# L9110_v1_1.net
KiCad netlist of a schematic drawn in EAGLE
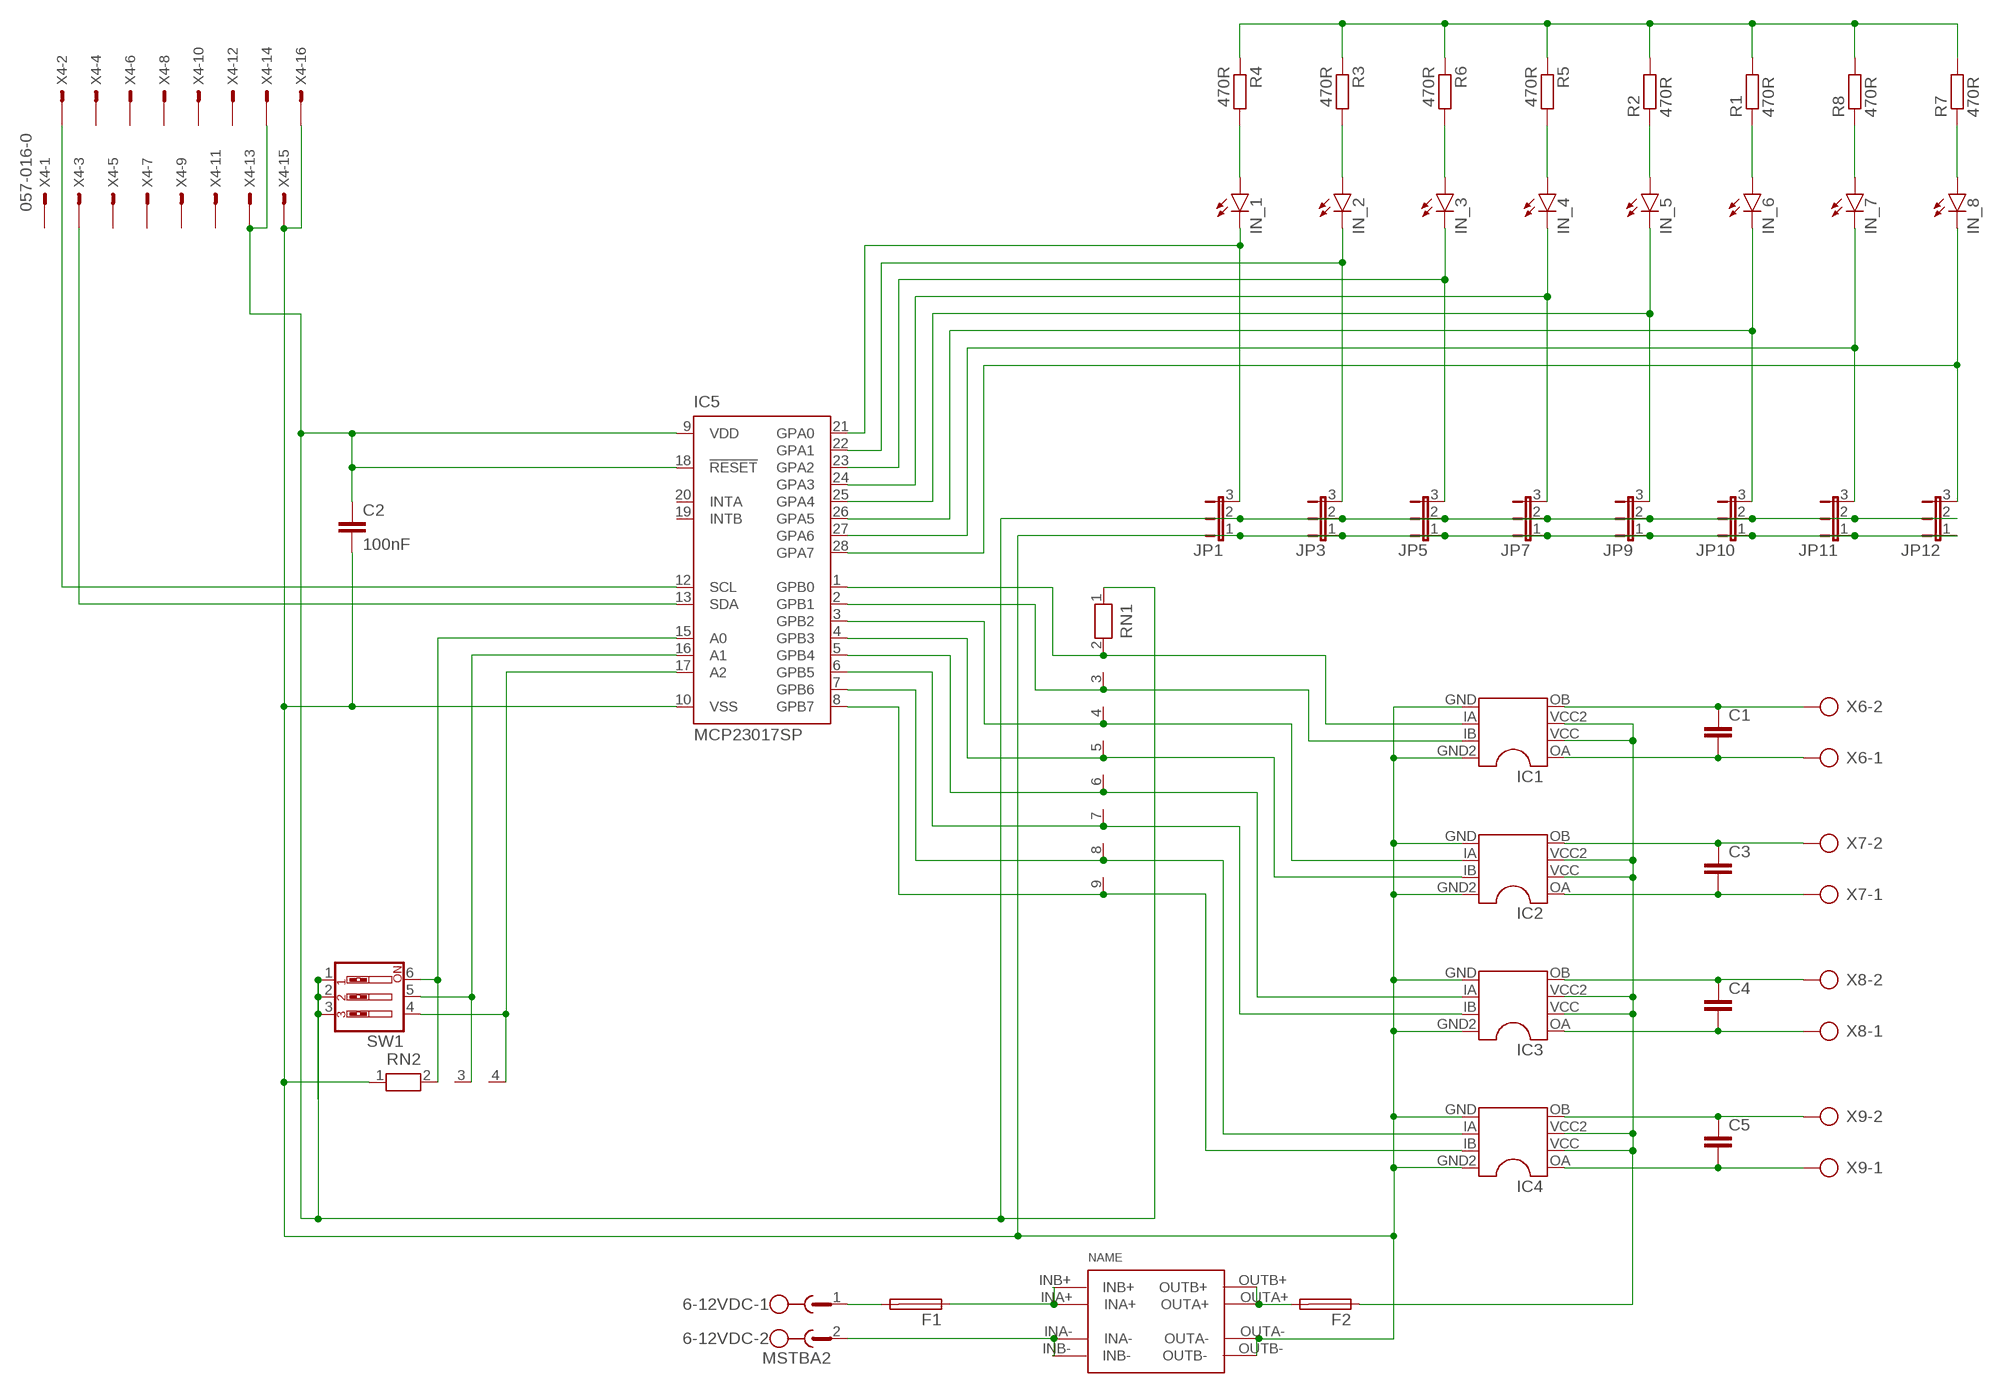
[diagram p0: schematic, sheet 1]

(export (version "E")
  (design (tool "Eeschema 10.0.6"))
  (components
    (comp (ref "6-12VDC")
      (value "MSTBA2")
      (footprint "eagle-import:MSTBA2")
      (fields (field (name "MF") "FARNELL") (field (name "MPN") "1757242"))
      (libsource (lib "eagle-import") (part "MSTBA2"))
    )
    (comp (ref "C1")
      (value "C-EU025-024X044")
      (footprint "eagle-import:C025-024X044")
      (libsource (lib "eagle-import") (part "C-EU025-024X044"))
    )
    (comp (ref "C2")
      (value "100nF")
      (footprint "eagle-import:C025-024X044")
      (libsource (lib "eagle-import") (part "C-EU025-024X044"))
    )
    (comp (ref "C3")
      (value "C-EU025-024X044")
      (footprint "eagle-import:C025-024X044")
      (libsource (lib "eagle-import") (part "C-EU025-024X044"))
    )
    (comp (ref "C4")
      (value "C-EU025-024X044")
      (footprint "eagle-import:C025-024X044")
      (libsource (lib "eagle-import") (part "C-EU025-024X044"))
    )
    (comp (ref "C5")
      (value "C-EU025-024X044")
      (footprint "eagle-import:C025-024X044")
      (libsource (lib "eagle-import") (part "C-EU025-024X044"))
    )
    (comp (ref "F1")
      (value "SH22,5A")
      (footprint "eagle-import:SH22,5A")
      (fields (field (name "MPN") "0031.7701.11"))
      (libsource (lib "eagle-import") (part "SH22,5A"))
    )
    (comp (ref "F2")
      (value "SH22,5A")
      (footprint "eagle-import:SH22,5A")
      (fields (field (name "MPN") "0031.7701.11"))
      (libsource (lib "eagle-import") (part "SH22,5A"))
    )
    (comp (ref "IC1")
      (value "L9110")
      (footprint "eagle-import:L9110")
      (libsource (lib "eagle-import") (part "L9110"))
    )
    (comp (ref "IC2")
      (value "L9110")
      (footprint "eagle-import:L9110")
      (libsource (lib "eagle-import") (part "L9110"))
    )
    (comp (ref "IC3")
      (value "L9110")
      (footprint "eagle-import:L9110")
      (libsource (lib "eagle-import") (part "L9110"))
    )
    (comp (ref "IC4")
      (value "L9110")
      (footprint "eagle-import:L9110")
      (libsource (lib "eagle-import") (part "L9110"))
    )
    (comp (ref "IC5")
      (value "MCP23017SP")
      (footprint "eagle-import:DIL28-3")
      (libsource (lib "eagle-import") (part "MCP23017SP"))
    )
    (comp (ref "IN_1")
      (value "LED3MM")
      (footprint "eagle-import:LED3MM")
      (libsource (lib "eagle-import") (part "LED3MM"))
    )
    (comp (ref "IN_2")
      (value "LED3MM")
      (footprint "eagle-import:LED3MM")
      (libsource (lib "eagle-import") (part "LED3MM"))
    )
    (comp (ref "IN_3")
      (value "LED3MM")
      (footprint "eagle-import:LED3MM")
      (libsource (lib "eagle-import") (part "LED3MM"))
    )
    (comp (ref "IN_4")
      (value "LED3MM")
      (footprint "eagle-import:LED3MM")
      (libsource (lib "eagle-import") (part "LED3MM"))
    )
    (comp (ref "IN_5")
      (value "LED3MM")
      (footprint "eagle-import:LED3MM")
      (libsource (lib "eagle-import") (part "LED3MM"))
    )
    (comp (ref "IN_6")
      (value "LED3MM")
      (footprint "eagle-import:LED3MM")
      (libsource (lib "eagle-import") (part "LED3MM"))
    )
    (comp (ref "IN_7")
      (value "LED3MM")
      (footprint "eagle-import:LED3MM")
      (libsource (lib "eagle-import") (part "LED3MM"))
    )
    (comp (ref "IN_8")
      (value "LED3MM")
      (footprint "eagle-import:LED3MM")
      (libsource (lib "eagle-import") (part "LED3MM"))
    )
    (comp (ref "JP1")
      (value "JP2E")
      (footprint "eagle-import:JP2")
      (libsource (lib "eagle-import") (part "JP2E"))
    )
    (comp (ref "JP3")
      (value "JP2E")
      (footprint "eagle-import:JP2")
      (libsource (lib "eagle-import") (part "JP2E"))
    )
    (comp (ref "JP5")
      (value "JP2E")
      (footprint "eagle-import:JP2")
      (libsource (lib "eagle-import") (part "JP2E"))
    )
    (comp (ref "JP7")
      (value "JP2E")
      (footprint "eagle-import:JP2")
      (libsource (lib "eagle-import") (part "JP2E"))
    )
    (comp (ref "JP9")
      (value "JP2E")
      (footprint "eagle-import:JP2")
      (libsource (lib "eagle-import") (part "JP2E"))
    )
    (comp (ref "JP10")
      (value "JP2E")
      (footprint "eagle-import:JP2")
      (libsource (lib "eagle-import") (part "JP2E"))
    )
    (comp (ref "JP11")
      (value "JP2E")
      (footprint "eagle-import:JP2")
      (libsource (lib "eagle-import") (part "JP2E"))
    )
    (comp (ref "JP12")
      (value "JP2E")
      (footprint "eagle-import:JP2")
      (libsource (lib "eagle-import") (part "JP2E"))
    )
    (comp (ref "R1")
      (value "470R")
      (footprint "eagle-import:0309_10")
      (libsource (lib "eagle-import") (part "R-EU_0309/10"))
    )
    (comp (ref "R2")
      (value "470R")
      (footprint "eagle-import:0309_10")
      (libsource (lib "eagle-import") (part "R-EU_0309/10"))
    )
    (comp (ref "R3")
      (value "470R")
      (footprint "eagle-import:0309_10")
      (libsource (lib "eagle-import") (part "R-EU_0309/10"))
    )
    (comp (ref "R4")
      (value "470R")
      (footprint "eagle-import:0309_10")
      (libsource (lib "eagle-import") (part "R-EU_0309/10"))
    )
    (comp (ref "R5")
      (value "470R")
      (footprint "eagle-import:0309_10")
      (libsource (lib "eagle-import") (part "R-EU_0309/10"))
    )
    (comp (ref "R6")
      (value "470R")
      (footprint "eagle-import:0309_10")
      (libsource (lib "eagle-import") (part "R-EU_0309/10"))
    )
    (comp (ref "R7")
      (value "470R")
      (footprint "eagle-import:0309_10")
      (libsource (lib "eagle-import") (part "R-EU_0309/10"))
    )
    (comp (ref "R8")
      (value "470R")
      (footprint "eagle-import:0309_10")
      (libsource (lib "eagle-import") (part "R-EU_0309/10"))
    )
    (comp (ref "RN1")
      (value "RN08")
      (footprint "eagle-import:RN-9")
      (libsource (lib "eagle-import") (part "RN08"))
    )
    (comp (ref "RN2")
      (value "RN03")
      (footprint "eagle-import:RN-3")
      (libsource (lib "eagle-import") (part "RN03"))
    )
    (comp (ref "SW1")
      (value "SW_DIP-3")
      (footprint "eagle-import:EDG-03")
      (libsource (lib "eagle-import") (part "SW_DIP-3"))
    )
    (comp (ref "U$2")
      (value "CP8-ADJ-B")
      (footprint "eagle-import:CP8-ADJ-B")
      (libsource (lib "eagle-import") (part "CP8-ADJ-B"))
    )
    (comp (ref "X4")
      (value "057-016-0")
      (footprint "eagle-import:057-016-0")
      (libsource (lib "eagle-import") (part "057-016-0"))
    )
    (comp (ref "X6")
      (value "AK300/2")
      (footprint "eagle-import:AK300_2")
      (libsource (lib "eagle-import") (part "AK300/2"))
    )
    (comp (ref "X7")
      (value "AK300/2")
      (footprint "eagle-import:AK300_2")
      (libsource (lib "eagle-import") (part "AK300/2"))
    )
    (comp (ref "X8")
      (value "AK300/2")
      (footprint "eagle-import:AK300_2")
      (libsource (lib "eagle-import") (part "AK300/2"))
    )
    (comp (ref "X9")
      (value "AK300/2")
      (footprint "eagle-import:AK300_2")
      (libsource (lib "eagle-import") (part "AK300/2"))
    )
  )
  (nets
    (net (code "1") (name "Net-(6-12VDC-Pad1)") (class "Default")
      (node (ref "6-12VDC") (pin "1") (pinfunction "1_1") (pintype "passive"))
      (node (ref "F1") (pin "2") (pinfunction "2_2") (pintype "passive"))
    )
    (net (code "2") (name "Net-(6-12VDCB-1)") (class "Default")
      (node (ref "6-12VDC") (pin "2") (pinfunction "1_2") (pintype "passive"))
      (node (ref "U$2") (pin "INA-") (pinfunction "INA-_INA-") (pintype "passive"))
      (node (ref "U$2") (pin "INB-") (pinfunction "INB-_INB-") (pintype "passive"))
    )
    (net (code "3") (name "Net-(F1-Pad1)") (class "Default")
      (node (ref "F1") (pin "1") (pinfunction "1_1") (pintype "passive"))
      (node (ref "U$2") (pin "INA+") (pinfunction "INA+_INA+") (pintype "passive"))
      (node (ref "U$2") (pin "INB+") (pinfunction "INB+_INB+") (pintype "passive"))
    )
    (net (code "4") (name "Net-(F2-Pad2)") (class "Default")
      (node (ref "F2") (pin "2") (pinfunction "2_2") (pintype "passive"))
      (node (ref "U$2") (pin "OUTA+") (pinfunction "OUTA+_OUTA+") (pintype "passive"))
      (node (ref "U$2") (pin "OUTB+") (pinfunction "OUTB+_OUTB+") (pintype "passive"))
    )
    (net (code "5") (name "Net-(IC1-1)") (class "Default")
      (node (ref "C1") (pin "2") (pinfunction "2_2") (pintype "passive"))
      (node (ref "IC1") (pin "OA") (pinfunction "1_OA") (pintype "passive"))
      (node (ref "X6") (pin "1") (pinfunction "KL_1") (pintype "passive"))
    )
    (net (code "6") (name "Net-(IC1-2)") (class "Default")
      (node (ref "F2") (pin "1") (pinfunction "1_1") (pintype "passive"))
      (node (ref "IC1") (pin "VCC") (pinfunction "2_VCC") (pintype "passive"))
      (node (ref "IC1") (pin "VCC2") (pinfunction "3_VCC2") (pintype "passive"))
      (node (ref "IC2") (pin "VCC") (pinfunction "2_VCC") (pintype "passive"))
      (node (ref "IC2") (pin "VCC2") (pinfunction "3_VCC2") (pintype "passive"))
      (node (ref "IC3") (pin "VCC") (pinfunction "2_VCC") (pintype "passive"))
      (node (ref "IC3") (pin "VCC2") (pinfunction "3_VCC2") (pintype "passive"))
      (node (ref "IC4") (pin "VCC") (pinfunction "2_VCC") (pintype "passive"))
      (node (ref "IC4") (pin "VCC2") (pinfunction "3_VCC2") (pintype "passive"))
    )
    (net (code "7") (name "Net-(IC1-4)") (class "Default")
      (node (ref "C1") (pin "1") (pinfunction "1_1") (pintype "passive"))
      (node (ref "IC1") (pin "OB") (pinfunction "4_OB") (pintype "passive"))
      (node (ref "X6") (pin "2") (pinfunction "KL_2") (pintype "passive"))
    )
    (net (code "8") (name "Net-(IC1-5)") (class "Default")
      (node (ref "C2") (pin "2") (pinfunction "2_2") (pintype "passive"))
      (node (ref "IC1") (pin "GND") (pinfunction "5_GND") (pintype "passive"))
      (node (ref "IC1") (pin "GND2") (pinfunction "8_GND2") (pintype "passive"))
      (node (ref "IC2") (pin "GND") (pinfunction "5_GND") (pintype "passive"))
      (node (ref "IC2") (pin "GND2") (pinfunction "8_GND2") (pintype "passive"))
      (node (ref "IC3") (pin "GND") (pinfunction "5_GND") (pintype "passive"))
      (node (ref "IC3") (pin "GND2") (pinfunction "8_GND2") (pintype "passive"))
      (node (ref "IC4") (pin "GND") (pinfunction "5_GND") (pintype "passive"))
      (node (ref "IC4") (pin "GND2") (pinfunction "8_GND2") (pintype "passive"))
      (node (ref "IC5") (pin "10") (pinfunction "VSS_10") (pintype "power_in"))
      (node (ref "JP1") (pin "1") (pinfunction "1_1") (pintype "passive"))
      (node (ref "JP10") (pin "1") (pinfunction "1_1") (pintype "passive"))
      (node (ref "JP11") (pin "1") (pinfunction "1_1") (pintype "passive"))
      (node (ref "JP12") (pin "1") (pinfunction "1_1") (pintype "passive"))
      (node (ref "JP3") (pin "1") (pinfunction "1_1") (pintype "passive"))
      (node (ref "JP5") (pin "1") (pinfunction "1_1") (pintype "passive"))
      (node (ref "JP7") (pin "1") (pinfunction "1_1") (pintype "passive"))
      (node (ref "JP9") (pin "1") (pinfunction "1_1") (pintype "passive"))
      (node (ref "RN2") (pin "1") (pinfunction "1_1") (pintype "passive"))
      (node (ref "U$2") (pin "OUTA-") (pinfunction "OUTA-_OUTA-") (pintype "passive"))
      (node (ref "U$2") (pin "OUTB-") (pinfunction "OUTB-_OUTB-") (pintype "bidirectional"))
      (node (ref "X4") (pin "15") (pinfunction "S_15") (pintype "passive"))
      (node (ref "X4") (pin "16") (pinfunction "S_16") (pintype "passive"))
    )
    (net (code "9") (name "Net-(IC1-6)") (class "Default")
      (node (ref "IC1") (pin "IA") (pinfunction "6_IA") (pintype "passive"))
      (node (ref "IC5") (pin "1") (pinfunction "GPB0_1") (pintype "bidirectional"))
      (node (ref "RN1") (pin "2") (pinfunction "2_2") (pintype "passive"))
    )
    (net (code "10") (name "Net-(IC1-7)") (class "Default")
      (node (ref "IC1") (pin "IB") (pinfunction "7_IB") (pintype "passive"))
      (node (ref "IC5") (pin "2") (pinfunction "GPB1_2") (pintype "bidirectional"))
      (node (ref "RN1") (pin "3") (pinfunction "3_3") (pintype "passive"))
    )
    (net (code "11") (name "Net-(IC2-1)") (class "Default")
      (node (ref "C3") (pin "2") (pinfunction "2_2") (pintype "passive"))
      (node (ref "IC2") (pin "OA") (pinfunction "1_OA") (pintype "passive"))
      (node (ref "X7") (pin "1") (pinfunction "KL_1") (pintype "passive"))
    )
    (net (code "12") (name "Net-(IC2-4)") (class "Default")
      (node (ref "C3") (pin "1") (pinfunction "1_1") (pintype "passive"))
      (node (ref "IC2") (pin "OB") (pinfunction "4_OB") (pintype "passive"))
      (node (ref "X7") (pin "2") (pinfunction "KL_2") (pintype "passive"))
    )
    (net (code "13") (name "Net-(IC2-6)") (class "Default")
      (node (ref "IC2") (pin "IA") (pinfunction "6_IA") (pintype "passive"))
      (node (ref "IC5") (pin "3") (pinfunction "GPB2_3") (pintype "bidirectional"))
      (node (ref "RN1") (pin "4") (pinfunction "4_4") (pintype "passive"))
    )
    (net (code "14") (name "Net-(IC2-7)") (class "Default")
      (node (ref "IC2") (pin "IB") (pinfunction "7_IB") (pintype "passive"))
      (node (ref "IC5") (pin "4") (pinfunction "GPB3_4") (pintype "bidirectional"))
      (node (ref "RN1") (pin "5") (pinfunction "5_5") (pintype "passive"))
    )
    (net (code "15") (name "Net-(IC3-1)") (class "Default")
      (node (ref "C4") (pin "2") (pinfunction "2_2") (pintype "passive"))
      (node (ref "IC3") (pin "OA") (pinfunction "1_OA") (pintype "passive"))
      (node (ref "X8") (pin "1") (pinfunction "KL_1") (pintype "passive"))
    )
    (net (code "16") (name "Net-(IC3-4)") (class "Default")
      (node (ref "C4") (pin "1") (pinfunction "1_1") (pintype "passive"))
      (node (ref "IC3") (pin "OB") (pinfunction "4_OB") (pintype "passive"))
      (node (ref "X8") (pin "2") (pinfunction "KL_2") (pintype "passive"))
    )
    (net (code "17") (name "Net-(IC3-6)") (class "Default")
      (node (ref "IC3") (pin "IA") (pinfunction "6_IA") (pintype "passive"))
      (node (ref "IC5") (pin "5") (pinfunction "GPB4_5") (pintype "bidirectional"))
      (node (ref "RN1") (pin "6") (pinfunction "6_6") (pintype "passive"))
    )
    (net (code "18") (name "Net-(IC3-7)") (class "Default")
      (node (ref "IC3") (pin "IB") (pinfunction "7_IB") (pintype "passive"))
      (node (ref "IC5") (pin "6") (pinfunction "GPB5_6") (pintype "bidirectional"))
      (node (ref "RN1") (pin "7") (pinfunction "7_7") (pintype "passive"))
    )
    (net (code "19") (name "Net-(IC4-1)") (class "Default")
      (node (ref "C5") (pin "2") (pinfunction "2_2") (pintype "passive"))
      (node (ref "IC4") (pin "OA") (pinfunction "1_OA") (pintype "passive"))
      (node (ref "X9") (pin "1") (pinfunction "KL_1") (pintype "passive"))
    )
    (net (code "20") (name "Net-(IC4-4)") (class "Default")
      (node (ref "C5") (pin "1") (pinfunction "1_1") (pintype "passive"))
      (node (ref "IC4") (pin "OB") (pinfunction "4_OB") (pintype "passive"))
      (node (ref "X9") (pin "2") (pinfunction "KL_2") (pintype "passive"))
    )
    (net (code "21") (name "Net-(IC4-6)") (class "Default")
      (node (ref "IC4") (pin "IA") (pinfunction "6_IA") (pintype "passive"))
      (node (ref "IC5") (pin "7") (pinfunction "GPB6_7") (pintype "bidirectional"))
      (node (ref "RN1") (pin "8") (pinfunction "8_8") (pintype "passive"))
    )
    (net (code "22") (name "Net-(IC4-7)") (class "Default")
      (node (ref "IC4") (pin "IB") (pinfunction "7_IB") (pintype "passive"))
      (node (ref "IC5") (pin "8") (pinfunction "GPB7_8") (pintype "bidirectional"))
      (node (ref "RN1") (pin "9") (pinfunction "9_9") (pintype "passive"))
    )
    (net (code "23") (name "Net-(IC5-A0)") (class "Default")
      (node (ref "IC5") (pin "15") (pinfunction "A0_15") (pintype "input"))
      (node (ref "RN2") (pin "2") (pinfunction "2_2") (pintype "passive"))
      (node (ref "SW1") (pin "6") (pinfunction "6_6") (pintype "passive"))
    )
    (net (code "24") (name "Net-(IC5-A1)") (class "Default")
      (node (ref "IC5") (pin "16") (pinfunction "A1_16") (pintype "input"))
      (node (ref "RN2") (pin "3") (pinfunction "3_3") (pintype "passive"))
      (node (ref "SW1") (pin "5") (pinfunction "5_5") (pintype "passive"))
    )
    (net (code "25") (name "Net-(IC5-A2)") (class "Default")
      (node (ref "IC5") (pin "17") (pinfunction "A2_17") (pintype "input"))
      (node (ref "RN2") (pin "4") (pinfunction "4_4") (pintype "passive"))
      (node (ref "SW1") (pin "4") (pinfunction "4_4") (pintype "passive"))
    )
    (net (code "26") (name "Net-(IC5-GPA0)") (class "Default")
      (node (ref "IC5") (pin "21") (pinfunction "GPA0_21") (pintype "bidirectional"))
      (node (ref "IN_1") (pin "K") (pinfunction "C_K") (pintype "passive"))
      (node (ref "JP1") (pin "3") (pinfunction "3_3") (pintype "passive"))
    )
    (net (code "27") (name "Net-(IC5-GPA1)") (class "Default")
      (node (ref "IC5") (pin "22") (pinfunction "GPA1_22") (pintype "bidirectional"))
      (node (ref "IN_2") (pin "K") (pinfunction "C_K") (pintype "passive"))
      (node (ref "JP3") (pin "3") (pinfunction "3_3") (pintype "passive"))
    )
    (net (code "28") (name "Net-(IC5-GPA2)") (class "Default")
      (node (ref "IC5") (pin "23") (pinfunction "GPA2_23") (pintype "bidirectional"))
      (node (ref "IN_3") (pin "K") (pinfunction "C_K") (pintype "passive"))
      (node (ref "JP5") (pin "3") (pinfunction "3_3") (pintype "passive"))
    )
    (net (code "29") (name "Net-(IC5-GPA3)") (class "Default")
      (node (ref "IC5") (pin "24") (pinfunction "GPA3_24") (pintype "bidirectional"))
      (node (ref "IN_4") (pin "K") (pinfunction "C_K") (pintype "passive"))
      (node (ref "JP7") (pin "3") (pinfunction "3_3") (pintype "passive"))
    )
    (net (code "30") (name "Net-(IC5-GPA4)") (class "Default")
      (node (ref "IC5") (pin "25") (pinfunction "GPA4_25") (pintype "bidirectional"))
      (node (ref "IN_5") (pin "K") (pinfunction "C_K") (pintype "passive"))
      (node (ref "JP9") (pin "3") (pinfunction "3_3") (pintype "passive"))
    )
    (net (code "31") (name "Net-(IC5-GPA5)") (class "Default")
      (node (ref "IC5") (pin "26") (pinfunction "GPA5_26") (pintype "bidirectional"))
      (node (ref "IN_6") (pin "K") (pinfunction "C_K") (pintype "passive"))
      (node (ref "JP10") (pin "3") (pinfunction "3_3") (pintype "passive"))
    )
    (net (code "32") (name "Net-(IC5-GPA6)") (class "Default")
      (node (ref "IC5") (pin "27") (pinfunction "GPA6_27") (pintype "bidirectional"))
      (node (ref "IN_7") (pin "K") (pinfunction "C_K") (pintype "passive"))
      (node (ref "JP11") (pin "3") (pinfunction "3_3") (pintype "passive"))
    )
    (net (code "33") (name "Net-(IC5-GPA7)") (class "Default")
      (node (ref "IC5") (pin "28") (pinfunction "GPA7_28") (pintype "bidirectional"))
      (node (ref "IN_8") (pin "K") (pinfunction "C_K") (pintype "passive"))
      (node (ref "JP12") (pin "3") (pinfunction "3_3") (pintype "passive"))
    )
    (net (code "34") (name "Net-(IC5-SCL)") (class "Default")
      (node (ref "IC5") (pin "12") (pinfunction "SCL_12") (pintype "input"))
      (node (ref "X4") (pin "2") (pinfunction "S_2") (pintype "passive"))
    )
    (net (code "35") (name "Net-(IC5-SDA)") (class "Default")
      (node (ref "IC5") (pin "13") (pinfunction "SDA_13") (pintype "bidirectional"))
      (node (ref "X4") (pin "3") (pinfunction "S_3") (pintype "passive"))
    )
    (net (code "36") (name "Net-(IC5-VDD)") (class "Default")
      (node (ref "C2") (pin "1") (pinfunction "1_1") (pintype "passive"))
      (node (ref "IC5") (pin "18") (pinfunction "~{RESET}_18") (pintype "input"))
      (node (ref "IC5") (pin "9") (pinfunction "VDD_9") (pintype "power_in"))
      (node (ref "JP1") (pin "2") (pinfunction "2_2") (pintype "passive"))
      (node (ref "JP10") (pin "2") (pinfunction "2_2") (pintype "passive"))
      (node (ref "JP11") (pin "2") (pinfunction "2_2") (pintype "passive"))
      (node (ref "JP12") (pin "2") (pinfunction "2_2") (pintype "passive"))
      (node (ref "JP3") (pin "2") (pinfunction "2_2") (pintype "passive"))
      (node (ref "JP5") (pin "2") (pinfunction "2_2") (pintype "passive"))
      (node (ref "JP7") (pin "2") (pinfunction "2_2") (pintype "passive"))
      (node (ref "JP9") (pin "2") (pinfunction "2_2") (pintype "passive"))
      (node (ref "RN1") (pin "1") (pinfunction "1_1") (pintype "passive"))
      (node (ref "SW1") (pin "1") (pinfunction "1_1") (pintype "passive"))
      (node (ref "SW1") (pin "2") (pinfunction "2_2") (pintype "passive"))
      (node (ref "SW1") (pin "3") (pinfunction "3_3") (pintype "passive"))
      (node (ref "X4") (pin "13") (pinfunction "S_13") (pintype "passive"))
      (node (ref "X4") (pin "14") (pinfunction "S_14") (pintype "passive"))
    )
    (net (code "37") (name "Net-(IN_1-PadA)") (class "Default")
      (node (ref "IN_1") (pin "A") (pinfunction "A_A") (pintype "passive"))
      (node (ref "R4") (pin "2") (pinfunction "2_2") (pintype "passive"))
    )
    (net (code "38") (name "Net-(IN_2-PadA)") (class "Default")
      (node (ref "IN_2") (pin "A") (pinfunction "A_A") (pintype "passive"))
      (node (ref "R3") (pin "2") (pinfunction "2_2") (pintype "passive"))
    )
    (net (code "39") (name "Net-(IN_3-PadA)") (class "Default")
      (node (ref "IN_3") (pin "A") (pinfunction "A_A") (pintype "passive"))
      (node (ref "R6") (pin "2") (pinfunction "2_2") (pintype "passive"))
    )
    (net (code "40") (name "Net-(IN_4-PadA)") (class "Default")
      (node (ref "IN_4") (pin "A") (pinfunction "A_A") (pintype "passive"))
      (node (ref "R5") (pin "2") (pinfunction "2_2") (pintype "passive"))
    )
    (net (code "41") (name "Net-(IN_5-PadA)") (class "Default")
      (node (ref "IN_5") (pin "A") (pinfunction "A_A") (pintype "passive"))
      (node (ref "R2") (pin "1") (pinfunction "1_1") (pintype "passive"))
    )
    (net (code "42") (name "Net-(IN_6-PadA)") (class "Default")
      (node (ref "IN_6") (pin "A") (pinfunction "A_A") (pintype "passive"))
      (node (ref "R1") (pin "1") (pinfunction "1_1") (pintype "passive"))
    )
    (net (code "43") (name "Net-(IN_7-PadA)") (class "Default")
      (node (ref "IN_7") (pin "A") (pinfunction "A_A") (pintype "passive"))
      (node (ref "R8") (pin "1") (pinfunction "1_1") (pintype "passive"))
    )
    (net (code "44") (name "Net-(IN_8-PadA)") (class "Default")
      (node (ref "IN_8") (pin "A") (pinfunction "A_A") (pintype "passive"))
      (node (ref "R7") (pin "1") (pinfunction "1_1") (pintype "passive"))
    )
    (net (code "45") (name "Net-(R1-Pad2)") (class "Default")
      (node (ref "R1") (pin "2") (pinfunction "2_2") (pintype "passive"))
      (node (ref "R2") (pin "2") (pinfunction "2_2") (pintype "passive"))
      (node (ref "R3") (pin "1") (pinfunction "1_1") (pintype "passive"))
      (node (ref "R4") (pin "1") (pinfunction "1_1") (pintype "passive"))
      (node (ref "R5") (pin "1") (pinfunction "1_1") (pintype "passive"))
      (node (ref "R6") (pin "1") (pinfunction "1_1") (pintype "passive"))
      (node (ref "R7") (pin "2") (pinfunction "2_2") (pintype "passive"))
      (node (ref "R8") (pin "2") (pinfunction "2_2") (pintype "passive"))
    )
    (net (code "46") (name "unconnected-(IC5-INTA-Pad20)") (class "Default")
      (node (ref "IC5") (pin "20") (pinfunction "INTA_20") (pintype "output"))
    )
    (net (code "47") (name "unconnected-(IC5-INTB-Pad19)") (class "Default")
      (node (ref "IC5") (pin "19") (pinfunction "INTB_19") (pintype "output"))
    )
    (net (code "48") (name "unconnected-(X4A-S-Pad1)") (class "Default")
      (node (ref "X4") (pin "1") (pinfunction "S_1") (pintype "passive"))
    )
    (net (code "49") (name "unconnected-(X4B-S-Pad10)") (class "Default")
      (node (ref "X4") (pin "10") (pinfunction "S_10") (pintype "passive"))
    )
    (net (code "50") (name "unconnected-(X4C-S-Pad11)") (class "Default")
      (node (ref "X4") (pin "11") (pinfunction "S_11") (pintype "passive"))
    )
    (net (code "51") (name "unconnected-(X4D-S-Pad12)") (class "Default")
      (node (ref "X4") (pin "12") (pinfunction "S_12") (pintype "passive"))
    )
    (net (code "52") (name "unconnected-(X4K-S-Pad4)") (class "Default")
      (node (ref "X4") (pin "4") (pinfunction "S_4") (pintype "passive"))
    )
    (net (code "53") (name "unconnected-(X4L-S-Pad5)") (class "Default")
      (node (ref "X4") (pin "5") (pinfunction "S_5") (pintype "passive"))
    )
    (net (code "54") (name "unconnected-(X4M-S-Pad6)") (class "Default")
      (node (ref "X4") (pin "6") (pinfunction "S_6") (pintype "passive"))
    )
    (net (code "55") (name "unconnected-(X4N-S-Pad7)") (class "Default")
      (node (ref "X4") (pin "7") (pinfunction "S_7") (pintype "passive"))
    )
    (net (code "56") (name "unconnected-(X4O-S-Pad8)") (class "Default")
      (node (ref "X4") (pin "8") (pinfunction "S_8") (pintype "passive"))
    )
    (net (code "57") (name "unconnected-(X4P-S-Pad9)") (class "Default")
      (node (ref "X4") (pin "9") (pinfunction "S_9") (pintype "passive"))
    )
  )
)
